# miniCUP.net
KiCad netlist of a schematic drawn in Altium Designer
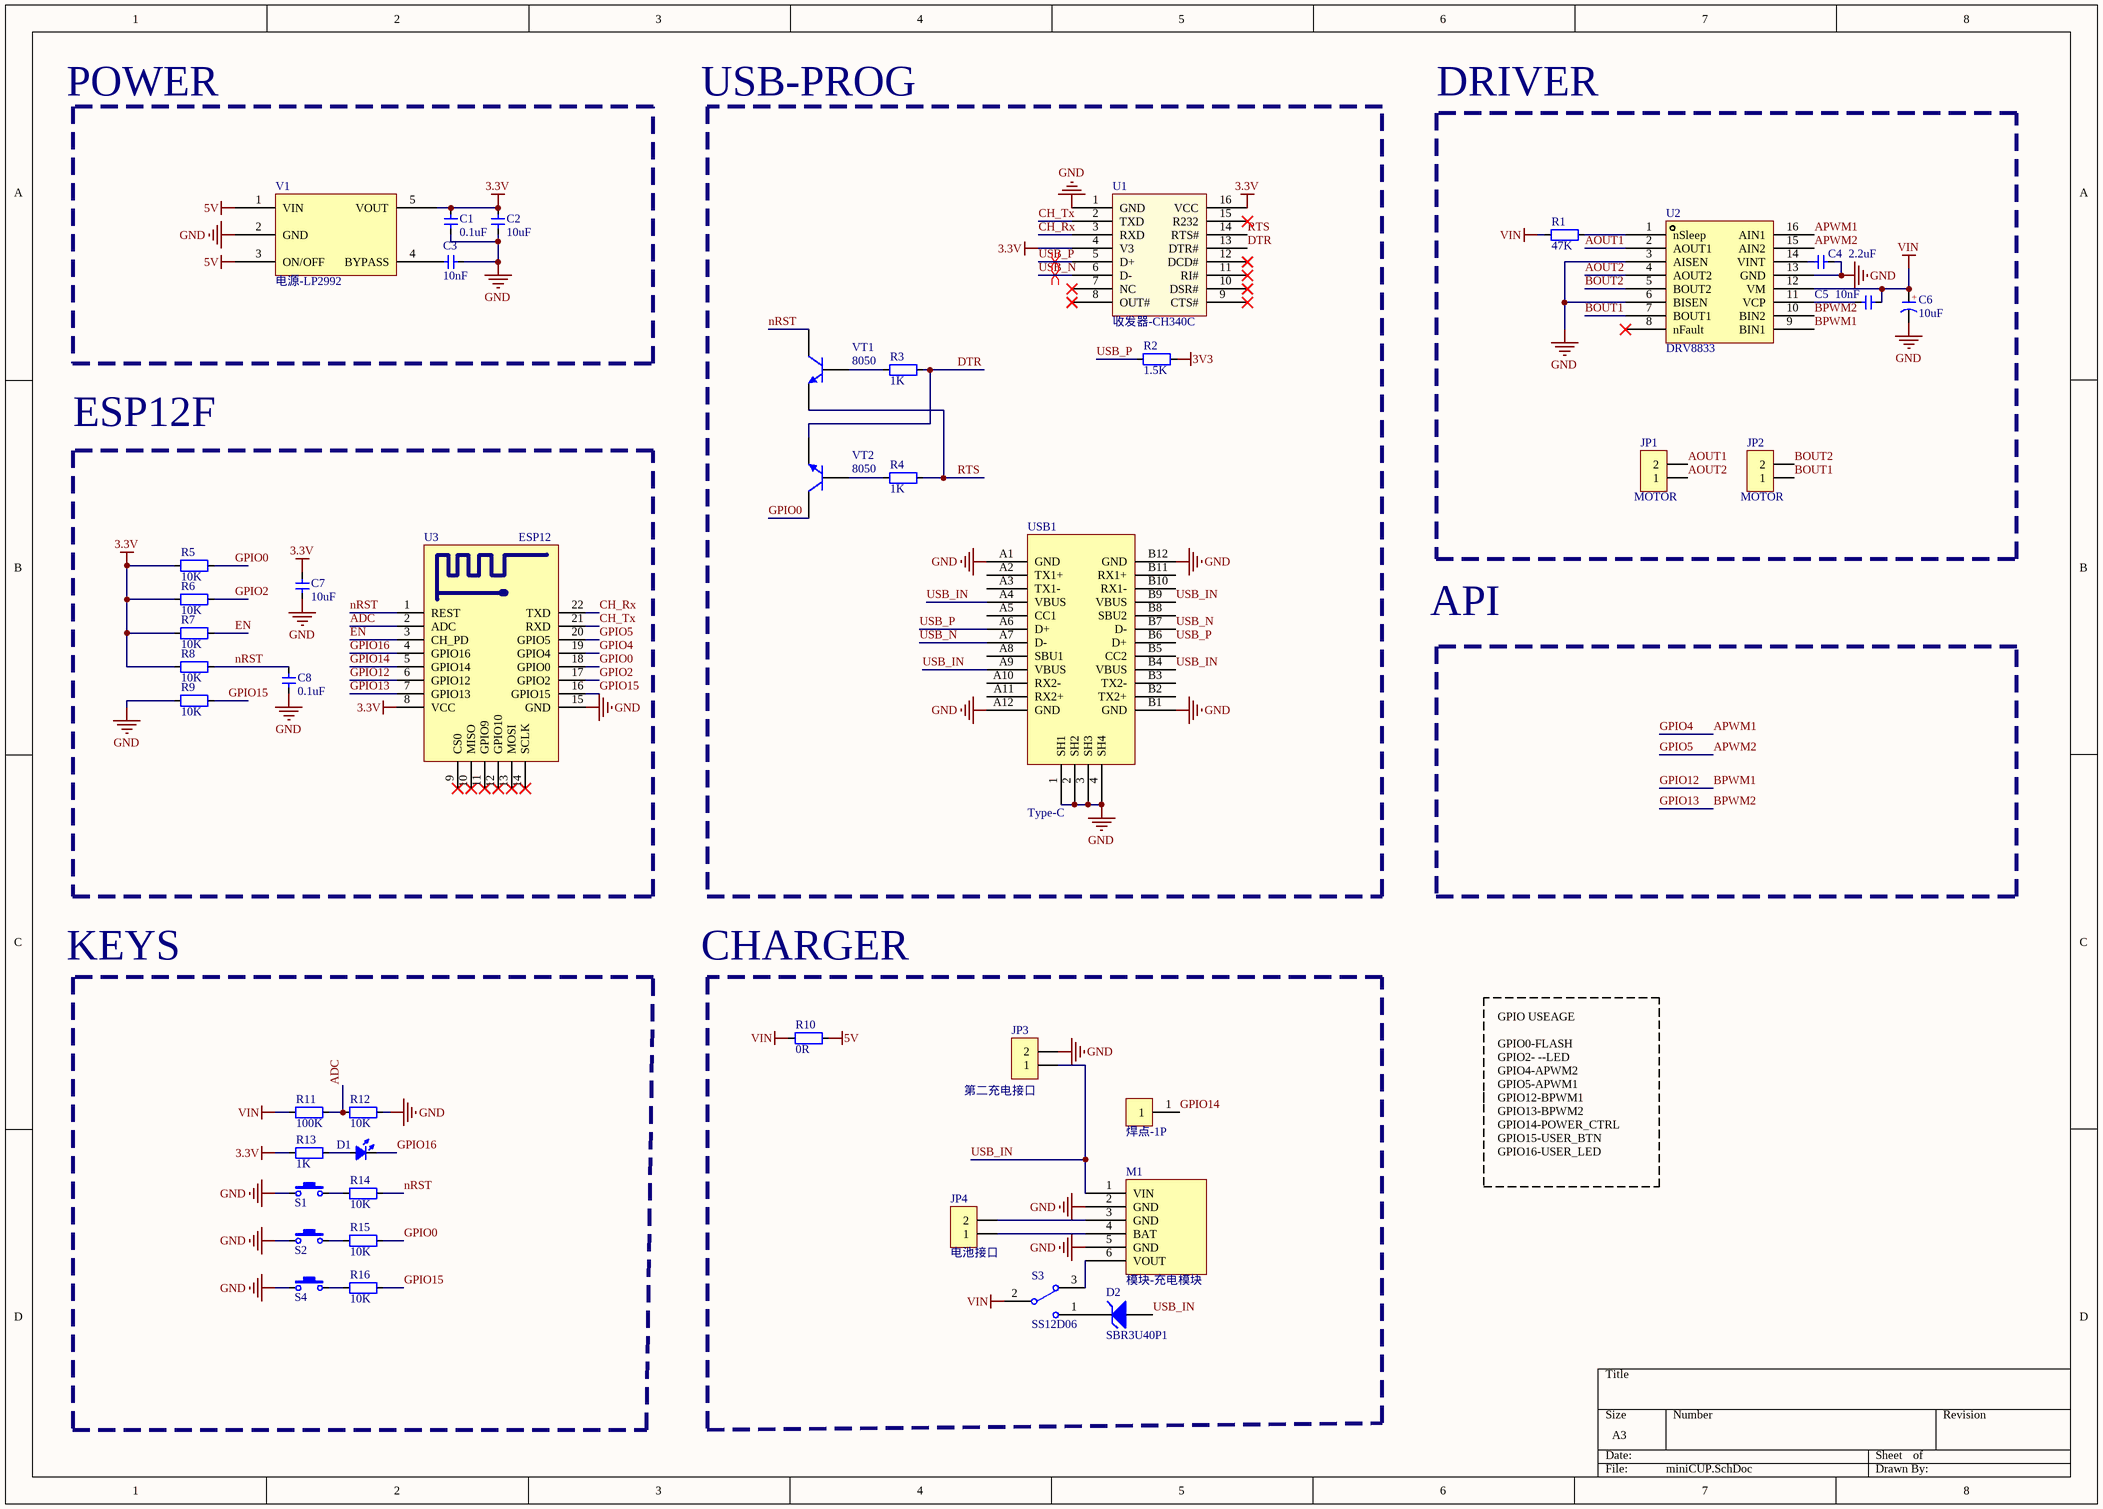
[diagram p0: miniCUP.SchDoc]

(export (version "E")
  (design (tool "Eeschema 10.0.6"))
  (components
    (comp (ref "*1")
      (value "焊点-1P")
      (footprint "Solder joints")
      (description "1P")
      (libsource (lib "0.0 - YltsSchlib") (part "焊点-1P"))
    )
    (comp (ref "C1")
      (value "0.1uF")
      (footprint "1.00-YltsPcbLib:0603_CAP")
      (description "电容")
      (libsource (lib "0.0 - YltsSchlib") (part "电容-0603"))
    )
    (comp (ref "C2")
      (value "10uF")
      (footprint "1.00-YltsPcbLib:0603_CAP")
      (description "电容")
      (libsource (lib "0.0 - YltsSchlib") (part "电容-0603"))
    )
    (comp (ref "C3")
      (value "10nF")
      (footprint "1.00-YltsPcbLib:0603_CAP")
      (description "电容")
      (libsource (lib "0.0 - YltsSchlib") (part "电容-0603"))
    )
    (comp (ref "C4")
      (value "2.2uF")
      (footprint "1.00-YltsPcbLib:0603_CAP")
      (description "电容")
      (libsource (lib "0.0 - YltsSchlib") (part "电容-0603"))
    )
    (comp (ref "C5")
      (value "10nF")
      (footprint "1.00-YltsPcbLib:0603_CAP")
      (description "电容")
      (libsource (lib "0.0 - YltsSchlib") (part "电容-0603"))
    )
    (comp (ref "C6")
      (value "10uF")
      (footprint "3528-CAP")
      (description "钽电容 A型")
      (fields (field (name "PUBLISHER") "Altium Limited"))
      (libsource (lib "0.0 - YltsSchlib") (part "电容-3216"))
    )
    (comp (ref "C7")
      (value "10uF")
      (footprint "1.00-YltsPcbLib:0603_CAP")
      (description "电容")
      (libsource (lib "0.0 - YltsSchlib") (part "电容-0603"))
    )
    (comp (ref "C8")
      (value "0.1uF")
      (footprint "1.00-YltsPcbLib:0603_CAP")
      (description "电容")
      (libsource (lib "0.0 - YltsSchlib") (part "电容-0603"))
    )
    (comp (ref "D1")
      (value "LED-0603")
      (footprint "1.00-YltsPcbLib:0603_LED_RED")
      (description "发光二极管")
      (libsource (lib "0.0 - YltsSchlib") (part "二极管-0603-RED"))
    )
    (comp (ref "D2")
      (value "SBR3U40P1")
      (footprint "D-POWERDI123")
      (description "Zener Diode")
      (libsource (lib "0.0 - YltsSchlib") (part "二极管-SBR3U40P1"))
    )
    (comp (ref "JP1")
      (value "MOTOR")
      (footprint "J-TIE-2-2.54")
      (description "2.54MM")
      (libsource (lib "0.0 - YltsSchlib") (part "接插件-TIE2.54-2P"))
    )
    (comp (ref "JP2")
      (value "MOTOR")
      (footprint "J-TIE-2-2.54")
      (description "2.54MM")
      (libsource (lib "0.0 - YltsSchlib") (part "接插件-TIE2.54-2P"))
    )
    (comp (ref "JP3")
      (value "第二充电接口")
      (footprint "J-TIE-2-2.54")
      (description "2.54MM")
      (libsource (lib "0.0 - YltsSchlib") (part "接插件-TIE2.54-2P"))
    )
    (comp (ref "JP4")
      (value "电池接口")
      (footprint "J-TIE-2-2.54")
      (description "2.54MM")
      (libsource (lib "0.0 - YltsSchlib") (part "接插件-TIE2.54-2P"))
    )
    (comp (ref "M1")
      (value "模块-充电模块")
      (footprint "模块-充电模块")
      (libsource (lib "0.0 - YltsSchlib") (part "模块-充电模块"))
    )
    (comp (ref "R1")
      (value "47K")
      (footprint "1.00-YltsPcbLib:0603_RES")
      (description "电阻")
      (libsource (lib "0.0 - YltsSchlib") (part "电阻-0603"))
    )
    (comp (ref "R2")
      (value "1.5K")
      (footprint "1.00-YltsPcbLib:0603_RES")
      (description "电阻")
      (libsource (lib "0.0 - YltsSchlib") (part "电阻-0603"))
    )
    (comp (ref "R3")
      (value "1K")
      (footprint "1.00-YltsPcbLib:0603_RES")
      (description "电阻")
      (libsource (lib "0.0 - YltsSchlib") (part "电阻-0603"))
    )
    (comp (ref "R4")
      (value "1K")
      (footprint "1.00-YltsPcbLib:0603_RES")
      (description "电阻")
      (libsource (lib "0.0 - YltsSchlib") (part "电阻-0603"))
    )
    (comp (ref "R5")
      (value "10K")
      (footprint "1.00-YltsPcbLib:0603_RES")
      (description "电阻")
      (libsource (lib "0.0 - YltsSchlib") (part "电阻-0603"))
    )
    (comp (ref "R6")
      (value "10K")
      (footprint "1.00-YltsPcbLib:0603_RES")
      (description "电阻")
      (libsource (lib "0.0 - YltsSchlib") (part "电阻-0603"))
    )
    (comp (ref "R7")
      (value "10K")
      (footprint "1.00-YltsPcbLib:0603_RES")
      (description "电阻")
      (libsource (lib "0.0 - YltsSchlib") (part "电阻-0603"))
    )
    (comp (ref "R8")
      (value "10K")
      (footprint "1.00-YltsPcbLib:0603_RES")
      (description "电阻")
      (libsource (lib "0.0 - YltsSchlib") (part "电阻-0603"))
    )
    (comp (ref "R9")
      (value "10K")
      (footprint "1.00-YltsPcbLib:0603_RES")
      (description "电阻")
      (libsource (lib "0.0 - YltsSchlib") (part "电阻-0603"))
    )
    (comp (ref "R10")
      (value "0R")
      (footprint "1.00-YltsPcbLib:0603_RES")
      (description "电阻")
      (libsource (lib "0.0 - YltsSchlib") (part "电阻-0603"))
    )
    (comp (ref "R11")
      (value "100K")
      (footprint "1.00-YltsPcbLib:0603_RES")
      (description "电阻")
      (libsource (lib "0.0 - YltsSchlib") (part "电阻-0603"))
    )
    (comp (ref "R12")
      (value "10K")
      (footprint "1.00-YltsPcbLib:0603_RES")
      (description "电阻")
      (libsource (lib "0.0 - YltsSchlib") (part "电阻-0603"))
    )
    (comp (ref "R13")
      (value "1K")
      (footprint "1.00-YltsPcbLib:0603_RES")
      (description "电阻")
      (libsource (lib "0.0 - YltsSchlib") (part "电阻-0603"))
    )
    (comp (ref "R14")
      (value "10K")
      (footprint "1.00-YltsPcbLib:0603_RES")
      (description "电阻")
      (libsource (lib "0.0 - YltsSchlib") (part "电阻-0603"))
    )
    (comp (ref "R15")
      (value "10K")
      (footprint "1.00-YltsPcbLib:0603_RES")
      (description "电阻")
      (libsource (lib "0.0 - YltsSchlib") (part "电阻-0603"))
    )
    (comp (ref "R16")
      (value "10K")
      (footprint "1.00-YltsPcbLib:0603_RES")
      (description "电阻")
      (libsource (lib "0.0 - YltsSchlib") (part "电阻-0603"))
    )
    (comp (ref "S1")
      (value "ButtonTACT_3x4x2_180")
      (footprint "ButtonTACT_3x4x2_180H")
      (description "3x4x2小龟角按键")
      (libsource (lib "0.0 - YltsSchlib") (part "按键-3x4x2"))
    )
    (comp (ref "S2")
      (value "ButtonTACT_3x4x2_180")
      (footprint "ButtonTACT_3x4x2_180H")
      (description "3x4x2小龟角按键")
      (libsource (lib "0.0 - YltsSchlib") (part "按键-3x4x2"))
    )
    (comp (ref "S3")
      (value "SS12D06")
      (footprint "SWITCH_4.3X8.6")
      (description "2档3脚 大电流拨动开关 弯脚")
      (libsource (lib "0.0 - YltsSchlib") (part "开关-SS12D06"))
    )
    (comp (ref "S4")
      (value "ButtonTACT_3x4x2_180")
      (footprint "ButtonTACT_3x4x2_180H")
      (description "3x4x2小龟角按键")
      (libsource (lib "0.0 - YltsSchlib") (part "按键-3x4x2"))
    )
    (comp (ref "U1")
      (value "收发器-CH340C")
      (footprint "SOIC-16")
      (description "USB转TTL，内置晶振")
      (libsource (lib "0.0 - YltsSchlib") (part "收发器-CH340C"))
    )
    (comp (ref "U2")
      (value "DRV8833")
      (footprint "TSSOP16_L")
      (description "2路直流电机驱动")
      (libsource (lib "0.0 - YltsSchlib") (part "驱动-DRV8833"))
    )
    (comp (ref "U3")
      (value "ESP12")
      (footprint "ESP12")
      (description "ESP12系列WIFI模块")
      (libsource (lib "0.0 - YltsSchlib") (part "通讯模组-ESP12"))
    )
    (comp (ref "USB1")
      (value "Type-C")
      (footprint "Type-C-TOP")
      (libsource (lib "0.0 - YltsSchlib") (part "接插件-USB-Type-C"))
    )
    (comp (ref "V1")
      (value "电源-LP2992")
      (footprint "SOT-23-5")
      (description "电源芯片")
      (libsource (lib "0.0 - YltsSchlib") (part "电源-LP2992"))
    )
    (comp (ref "VT1")
      (value "8050")
      (footprint "SOT-23-3")
      (fields (field (name "PUBLISHER") "Altium Limited"))
      (libsource (lib "0.0 - YltsSchlib") (part "三极管-S8050"))
    )
    (comp (ref "VT2")
      (value "8050")
      (footprint "SOT-23-3")
      (fields (field (name "PUBLISHER") "Altium Limited"))
      (libsource (lib "0.0 - YltsSchlib") (part "三极管-S8050"))
    )
  )
  (nets
    (net (code "1") (name "/ADC") (class "Default")
      (node (ref "R11") (pin "2") (pinfunction "2_2") (pintype "passive"))
      (node (ref "R12") (pin "1") (pinfunction "1_1") (pintype "passive"))
      (node (ref "U3") (pin "2") (pinfunction "ADC_2") (pintype "passive"))
    )
    (net (code "2") (name "/AOUT1") (class "Default")
      (node (ref "JP1") (pin "2") (pinfunction "2_2") (pintype "passive"))
      (node (ref "U2") (pin "2") (pinfunction "AOUT1_2") (pintype "passive"))
    )
    (net (code "3") (name "/AOUT2") (class "Default")
      (node (ref "JP1") (pin "1") (pinfunction "1_1") (pintype "passive"))
      (node (ref "U2") (pin "4") (pinfunction "AOUT2_4") (pintype "passive"))
    )
    (net (code "4") (name "/APWM1") (class "Default")
      (node (ref "U2") (pin "16") (pinfunction "AIN1_16") (pintype "passive"))
      (node (ref "U3") (pin "19") (pinfunction "GPIO4_19") (pintype "passive"))
    )
    (net (code "5") (name "/APWM2") (class "Default")
      (node (ref "U2") (pin "15") (pinfunction "AIN2_15") (pintype "passive"))
      (node (ref "U3") (pin "20") (pinfunction "GPIO5_20") (pintype "passive"))
    )
    (net (code "6") (name "/BOUT1") (class "Default")
      (node (ref "JP2") (pin "1") (pinfunction "1_1") (pintype "passive"))
      (node (ref "U2") (pin "7") (pinfunction "BOUT1_7") (pintype "passive"))
    )
    (net (code "7") (name "/BOUT2") (class "Default")
      (node (ref "JP2") (pin "2") (pinfunction "2_2") (pintype "passive"))
      (node (ref "U2") (pin "5") (pinfunction "BOUT2_5") (pintype "passive"))
    )
    (net (code "8") (name "/BPWM1") (class "Default")
      (node (ref "U2") (pin "9") (pinfunction "BIN1_9") (pintype "passive"))
      (node (ref "U3") (pin "6") (pinfunction "GPIO12_6") (pintype "passive"))
    )
    (net (code "9") (name "/BPWM2") (class "Default")
      (node (ref "U2") (pin "10") (pinfunction "BIN2_10") (pintype "passive"))
      (node (ref "U3") (pin "7") (pinfunction "GPIO13_7") (pintype "passive"))
    )
    (net (code "10") (name "/CH_Rx") (class "Default")
      (node (ref "U1") (pin "3") (pinfunction "RXD_3") (pintype "passive"))
      (node (ref "U3") (pin "22") (pinfunction "TXD_22") (pintype "passive"))
    )
    (net (code "11") (name "/CH_Tx") (class "Default")
      (node (ref "U1") (pin "2") (pinfunction "TXD_2") (pintype "passive"))
      (node (ref "U3") (pin "21") (pinfunction "RXD_21") (pintype "passive"))
    )
    (net (code "12") (name "/DTR") (class "Default")
      (node (ref "R3") (pin "2") (pinfunction "2_2") (pintype "passive"))
      (node (ref "U1") (pin "13") (pinfunction "DTR#_13") (pintype "passive"))
      (node (ref "VT2") (pin "2") (pinfunction "E_2") (pintype "passive"))
    )
    (net (code "13") (name "/EN") (class "Default")
      (node (ref "R7") (pin "2") (pinfunction "2_2") (pintype "passive"))
      (node (ref "U3") (pin "3") (pinfunction "CH_PD_3") (pintype "passive"))
    )
    (net (code "14") (name "/GPIO0") (class "Default")
      (node (ref "R15") (pin "2") (pinfunction "2_2") (pintype "passive"))
      (node (ref "R5") (pin "2") (pinfunction "2_2") (pintype "passive"))
      (node (ref "U3") (pin "18") (pinfunction "GPIO0_18") (pintype "passive"))
      (node (ref "VT2") (pin "3") (pinfunction "C_3") (pintype "passive"))
    )
    (net (code "15") (name "/GPIO2") (class "Default")
      (node (ref "R6") (pin "2") (pinfunction "2_2") (pintype "passive"))
      (node (ref "U3") (pin "17") (pinfunction "GPIO2_17") (pintype "passive"))
    )
    (net (code "16") (name "/GPIO14") (class "Default")
      (node (ref "*1") (pin "1") (pinfunction "1_1") (pintype "passive"))
      (node (ref "U3") (pin "5") (pinfunction "GPIO14_5") (pintype "passive"))
    )
    (net (code "17") (name "/GPIO15") (class "Default")
      (node (ref "R16") (pin "2") (pinfunction "2_2") (pintype "passive"))
      (node (ref "R9") (pin "2") (pinfunction "2_2") (pintype "passive"))
      (node (ref "U3") (pin "16") (pinfunction "GPIO15_16") (pintype "passive"))
    )
    (net (code "18") (name "/GPIO16") (class "Default")
      (node (ref "D1") (pin "2") (pinfunction "K_2") (pintype "passive"))
      (node (ref "U3") (pin "4") (pinfunction "GPIO16_4") (pintype "passive"))
    )
    (net (code "19") (name "/RTS") (class "Default")
      (node (ref "R4") (pin "2") (pinfunction "2_2") (pintype "passive"))
      (node (ref "U1") (pin "14") (pinfunction "RTS#_14") (pintype "passive"))
      (node (ref "VT1") (pin "2") (pinfunction "E_2") (pintype "passive"))
    )
    (net (code "20") (name "/USB_IN") (class "Default")
      (node (ref "D2") (pin "1") (pinfunction "A_1") (pintype "passive"))
      (node (ref "JP3") (pin "1") (pinfunction "1_1") (pintype "passive"))
      (node (ref "M1") (pin "1") (pinfunction "VIN_1") (pintype "passive"))
      (node (ref "USB1") (pin "A4") (pinfunction "VBUS_A4") (pintype "passive"))
      (node (ref "USB1") (pin "A9") (pinfunction "VBUS_A9") (pintype "passive"))
      (node (ref "USB1") (pin "B4") (pinfunction "VBUS_B4") (pintype "passive"))
      (node (ref "USB1") (pin "B9") (pinfunction "VBUS_B9") (pintype "passive"))
    )
    (net (code "21") (name "/USB_N") (class "Default")
      (node (ref "U1") (pin "6") (pinfunction "D-_6") (pintype "passive"))
      (node (ref "USB1") (pin "A7") (pinfunction "D-_A7") (pintype "passive"))
      (node (ref "USB1") (pin "B7") (pinfunction "D-_B7") (pintype "passive"))
    )
    (net (code "22") (name "/USB_P") (class "Default")
      (node (ref "R2") (pin "1") (pinfunction "1_1") (pintype "passive"))
      (node (ref "U1") (pin "5") (pinfunction "D+_5") (pintype "passive"))
      (node (ref "USB1") (pin "A6") (pinfunction "D+_A6") (pintype "passive"))
      (node (ref "USB1") (pin "B6") (pinfunction "D+_B6") (pintype "passive"))
    )
    (net (code "23") (name "/nRST") (class "Default")
      (node (ref "C8") (pin "2") (pinfunction "2_2") (pintype "passive"))
      (node (ref "R14") (pin "2") (pinfunction "2_2") (pintype "passive"))
      (node (ref "R8") (pin "2") (pinfunction "2_2") (pintype "passive"))
      (node (ref "U3") (pin "1") (pinfunction "REST_1") (pintype "passive"))
      (node (ref "VT1") (pin "3") (pinfunction "C_3") (pintype "passive"))
    )
    (net (code "24") (name "3.3V") (class "Default")
      (node (ref "C1") (pin "2") (pinfunction "2_2") (pintype "passive"))
      (node (ref "C2") (pin "2") (pinfunction "2_2") (pintype "passive"))
      (node (ref "C7") (pin "2") (pinfunction "2_2") (pintype "passive"))
      (node (ref "R13") (pin "1") (pinfunction "1_1") (pintype "passive"))
      (node (ref "R5") (pin "1") (pinfunction "1_1") (pintype "passive"))
      (node (ref "R6") (pin "1") (pinfunction "1_1") (pintype "passive"))
      (node (ref "R7") (pin "1") (pinfunction "1_1") (pintype "passive"))
      (node (ref "R8") (pin "1") (pinfunction "1_1") (pintype "passive"))
      (node (ref "U1") (pin "16") (pinfunction "VCC_16") (pintype "passive"))
      (node (ref "U1") (pin "4") (pinfunction "V3_4") (pintype "passive"))
      (node (ref "U3") (pin "8") (pinfunction "VCC_8") (pintype "passive"))
      (node (ref "V1") (pin "5") (pinfunction "VOUT_5") (pintype "passive"))
    )
    (net (code "25") (name "3V3") (class "Default")
      (node (ref "R2") (pin "2") (pinfunction "2_2") (pintype "passive"))
    )
    (net (code "26") (name "5V") (class "Default")
      (node (ref "R10") (pin "2") (pinfunction "2_2") (pintype "passive"))
      (node (ref "V1") (pin "1") (pinfunction "VIN_1") (pintype "passive"))
      (node (ref "V1") (pin "3") (pinfunction "ON/OFF_3") (pintype "passive"))
    )
    (net (code "27") (name "GND") (class "Default")
      (node (ref "C1") (pin "1") (pinfunction "1_1") (pintype "passive"))
      (node (ref "C2") (pin "1") (pinfunction "1_1") (pintype "passive"))
      (node (ref "C3") (pin "1") (pinfunction "1_1") (pintype "passive"))
      (node (ref "C4") (pin "2") (pinfunction "2_2") (pintype "passive"))
      (node (ref "C6") (pin "2") (pinfunction "K_2") (pintype "passive"))
      (node (ref "C7") (pin "1") (pinfunction "1_1") (pintype "passive"))
      (node (ref "C8") (pin "1") (pinfunction "1_1") (pintype "passive"))
      (node (ref "JP3") (pin "2") (pinfunction "2_2") (pintype "passive"))
      (node (ref "M1") (pin "2") (pinfunction "GND_2") (pintype "passive"))
      (node (ref "M1") (pin "5") (pinfunction "GND_5") (pintype "passive"))
      (node (ref "R12") (pin "2") (pinfunction "2_2") (pintype "passive"))
      (node (ref "R9") (pin "1") (pinfunction "1_1") (pintype "passive"))
      (node (ref "S1") (pin "1") (pinfunction "1_1") (pintype "passive"))
      (node (ref "S2") (pin "1") (pinfunction "1_1") (pintype "passive"))
      (node (ref "S4") (pin "1") (pinfunction "1_1") (pintype "passive"))
      (node (ref "U1") (pin "1") (pinfunction "GND_1") (pintype "passive"))
      (node (ref "U2") (pin "13") (pinfunction "GND_13") (pintype "passive"))
      (node (ref "U2") (pin "3") (pinfunction "AISEN_3") (pintype "passive"))
      (node (ref "U2") (pin "6") (pinfunction "BISEN_6") (pintype "passive"))
      (node (ref "U3") (pin "15") (pinfunction "GND_15") (pintype "passive"))
      (node (ref "USB1") (pin "1") (pinfunction "SH1_1") (pintype "passive"))
      (node (ref "USB1") (pin "2") (pinfunction "SH2_2") (pintype "passive"))
      (node (ref "USB1") (pin "3") (pinfunction "SH3_3") (pintype "passive"))
      (node (ref "USB1") (pin "4") (pinfunction "SH4_4") (pintype "passive"))
      (node (ref "USB1") (pin "A1") (pinfunction "GND_A1") (pintype "passive"))
      (node (ref "USB1") (pin "A12") (pinfunction "GND_A12") (pintype "passive"))
      (node (ref "USB1") (pin "B1") (pinfunction "GND_B1") (pintype "passive"))
      (node (ref "USB1") (pin "B12") (pinfunction "GND_B12") (pintype "passive"))
      (node (ref "V1") (pin "2") (pinfunction "GND_2") (pintype "passive"))
    )
    (net (code "28") (name "Net-(D1-A)") (class "Default")
      (node (ref "D1") (pin "1") (pinfunction "A_1") (pintype "passive"))
      (node (ref "R13") (pin "2") (pinfunction "2_2") (pintype "passive"))
    )
    (net (code "29") (name "Net-(D2-K)") (class "Default")
      (node (ref "D2") (pin "2") (pinfunction "K_2") (pintype "passive"))
      (node (ref "S3") (pin "1") (pinfunction "1_1") (pintype "passive"))
    )
    (net (code "30") (name "Net-(JP4-Pad2)") (class "Default")
      (node (ref "JP4") (pin "2") (pinfunction "2_2") (pintype "passive"))
      (node (ref "M1") (pin "3") (pinfunction "GND_3") (pintype "passive"))
    )
    (net (code "31") (name "Net-(M1-BAT)") (class "Default")
      (node (ref "JP4") (pin "1") (pinfunction "1_1") (pintype "passive"))
      (node (ref "M1") (pin "4") (pinfunction "BAT_4") (pintype "passive"))
    )
    (net (code "32") (name "Net-(M1-VOUT)") (class "Default")
      (node (ref "M1") (pin "6") (pinfunction "VOUT_6") (pintype "passive"))
      (node (ref "S3") (pin "3") (pinfunction "3_3") (pintype "passive"))
    )
    (net (code "33") (name "Net-(R14-Pad1)") (class "Default")
      (node (ref "R14") (pin "1") (pinfunction "1_1") (pintype "passive"))
      (node (ref "S1") (pin "2") (pinfunction "2_2") (pintype "passive"))
    )
    (net (code "34") (name "Net-(R15-Pad1)") (class "Default")
      (node (ref "R15") (pin "1") (pinfunction "1_1") (pintype "passive"))
      (node (ref "S2") (pin "2") (pinfunction "2_2") (pintype "passive"))
    )
    (net (code "35") (name "Net-(R16-Pad1)") (class "Default")
      (node (ref "R16") (pin "1") (pinfunction "1_1") (pintype "passive"))
      (node (ref "S4") (pin "2") (pinfunction "2_2") (pintype "passive"))
    )
    (net (code "36") (name "Net-(U2-VCP)") (class "Default")
      (node (ref "C5") (pin "1") (pinfunction "1_1") (pintype "passive"))
      (node (ref "U2") (pin "11") (pinfunction "VCP_11") (pintype "passive"))
    )
    (net (code "37") (name "Net-(U2-VINT)") (class "Default")
      (node (ref "C4") (pin "1") (pinfunction "1_1") (pintype "passive"))
      (node (ref "U2") (pin "14") (pinfunction "VINT_14") (pintype "passive"))
    )
    (net (code "38") (name "Net-(U2-nSleep)") (class "Default")
      (node (ref "R1") (pin "2") (pinfunction "2_2") (pintype "passive"))
      (node (ref "U2") (pin "1") (pinfunction "nSleep_1") (pintype "passive"))
    )
    (net (code "39") (name "Net-(V1-BYPASS)") (class "Default")
      (node (ref "C3") (pin "2") (pinfunction "2_2") (pintype "passive"))
      (node (ref "V1") (pin "4") (pinfunction "BYPASS_4") (pintype "passive"))
    )
    (net (code "40") (name "Net-(VT1-B)") (class "Default")
      (node (ref "R3") (pin "1") (pinfunction "1_1") (pintype "passive"))
      (node (ref "VT1") (pin "1") (pinfunction "B_1") (pintype "passive"))
    )
    (net (code "41") (name "Net-(VT2-B)") (class "Default")
      (node (ref "R4") (pin "1") (pinfunction "1_1") (pintype "passive"))
      (node (ref "VT2") (pin "1") (pinfunction "B_1") (pintype "passive"))
    )
    (net (code "42") (name "VIN") (class "Default")
      (node (ref "C5") (pin "2") (pinfunction "2_2") (pintype "passive"))
      (node (ref "C6") (pin "1") (pinfunction "A_1") (pintype "passive"))
      (node (ref "R1") (pin "1") (pinfunction "1_1") (pintype "passive"))
      (node (ref "R10") (pin "1") (pinfunction "1_1") (pintype "passive"))
      (node (ref "R11") (pin "1") (pinfunction "1_1") (pintype "passive"))
      (node (ref "S3") (pin "2") (pinfunction "2_2") (pintype "passive"))
      (node (ref "U2") (pin "12") (pinfunction "VM_12") (pintype "passive"))
    )
    (net (code "43") (name "unconnected-(U1-CTS#-Pad9)") (class "Default")
      (node (ref "U1") (pin "9") (pinfunction "CTS#_9") (pintype "passive+no_connect"))
    )
    (net (code "44") (name "unconnected-(U1-DCD#-Pad12)") (class "Default")
      (node (ref "U1") (pin "12") (pinfunction "DCD#_12") (pintype "passive+no_connect"))
    )
    (net (code "45") (name "unconnected-(U1-DSR#-Pad10)") (class "Default")
      (node (ref "U1") (pin "10") (pinfunction "DSR#_10") (pintype "passive+no_connect"))
    )
    (net (code "46") (name "unconnected-(U1-NC-Pad7)") (class "Default")
      (node (ref "U1") (pin "7") (pinfunction "NC_7") (pintype "passive+no_connect"))
    )
    (net (code "47") (name "unconnected-(U1-OUT#-Pad8)") (class "Default")
      (node (ref "U1") (pin "8") (pinfunction "OUT#_8") (pintype "passive+no_connect"))
    )
    (net (code "48") (name "unconnected-(U1-R232-Pad15)") (class "Default")
      (node (ref "U1") (pin "15") (pinfunction "R232_15") (pintype "passive+no_connect"))
    )
    (net (code "49") (name "unconnected-(U1-RI#-Pad11)") (class "Default")
      (node (ref "U1") (pin "11") (pinfunction "RI#_11") (pintype "passive+no_connect"))
    )
    (net (code "50") (name "unconnected-(U2-nFault-Pad8)") (class "Default")
      (node (ref "U2") (pin "8") (pinfunction "nFault_8") (pintype "passive+no_connect"))
    )
    (net (code "51") (name "unconnected-(U3-CS0-Pad9)") (class "Default")
      (node (ref "U3") (pin "9") (pinfunction "CS0_9") (pintype "passive+no_connect"))
    )
    (net (code "52") (name "unconnected-(U3-GPIO9-Pad11)") (class "Default")
      (node (ref "U3") (pin "11") (pinfunction "GPIO9_11") (pintype "passive+no_connect"))
    )
    (net (code "53") (name "unconnected-(U3-GPIO10-Pad12)") (class "Default")
      (node (ref "U3") (pin "12") (pinfunction "GPIO10_12") (pintype "passive+no_connect"))
    )
    (net (code "54") (name "unconnected-(U3-MISO-Pad10)") (class "Default")
      (node (ref "U3") (pin "10") (pinfunction "MISO_10") (pintype "passive+no_connect"))
    )
    (net (code "55") (name "unconnected-(U3-MOSI-Pad13)") (class "Default")
      (node (ref "U3") (pin "13") (pinfunction "MOSI_13") (pintype "passive+no_connect"))
    )
    (net (code "56") (name "unconnected-(U3-SCLK-Pad14)") (class "Default")
      (node (ref "U3") (pin "14") (pinfunction "SCLK_14") (pintype "passive+no_connect"))
    )
    (net (code "57") (name "unconnected-(USB1-CC1-PadA5)") (class "Default")
      (node (ref "USB1") (pin "A5") (pinfunction "CC1_A5") (pintype "passive"))
    )
    (net (code "58") (name "unconnected-(USB1-CC2-PadB5)") (class "Default")
      (node (ref "USB1") (pin "B5") (pinfunction "CC2_B5") (pintype "passive"))
    )
    (net (code "59") (name "unconnected-(USB1-RX1+-PadB11)") (class "Default")
      (node (ref "USB1") (pin "B11") (pinfunction "RX1+_B11") (pintype "passive"))
    )
    (net (code "60") (name "unconnected-(USB1-RX1--PadB10)") (class "Default")
      (node (ref "USB1") (pin "B10") (pinfunction "RX1-_B10") (pintype "passive"))
    )
    (net (code "61") (name "unconnected-(USB1-RX2+-PadA11)") (class "Default")
      (node (ref "USB1") (pin "A11") (pinfunction "RX2+_A11") (pintype "passive"))
    )
    (net (code "62") (name "unconnected-(USB1-RX2--PadA10)") (class "Default")
      (node (ref "USB1") (pin "A10") (pinfunction "RX2-_A10") (pintype "passive"))
    )
    (net (code "63") (name "unconnected-(USB1-SBU1-PadA8)") (class "Default")
      (node (ref "USB1") (pin "A8") (pinfunction "SBU1_A8") (pintype "passive"))
    )
    (net (code "64") (name "unconnected-(USB1-SBU2-PadB8)") (class "Default")
      (node (ref "USB1") (pin "B8") (pinfunction "SBU2_B8") (pintype "passive"))
    )
    (net (code "65") (name "unconnected-(USB1-TX1+-PadA2)") (class "Default")
      (node (ref "USB1") (pin "A2") (pinfunction "TX1+_A2") (pintype "passive"))
    )
    (net (code "66") (name "unconnected-(USB1-TX1--PadA3)") (class "Default")
      (node (ref "USB1") (pin "A3") (pinfunction "TX1-_A3") (pintype "passive"))
    )
    (net (code "67") (name "unconnected-(USB1-TX2+-PadB2)") (class "Default")
      (node (ref "USB1") (pin "B2") (pinfunction "TX2+_B2") (pintype "passive"))
    )
    (net (code "68") (name "unconnected-(USB1-TX2--PadB3)") (class "Default")
      (node (ref "USB1") (pin "B3") (pinfunction "TX2-_B3") (pintype "passive"))
    )
  )
)
